# Power.net
KiCad netlist of a schematic drawn in Altium Designer
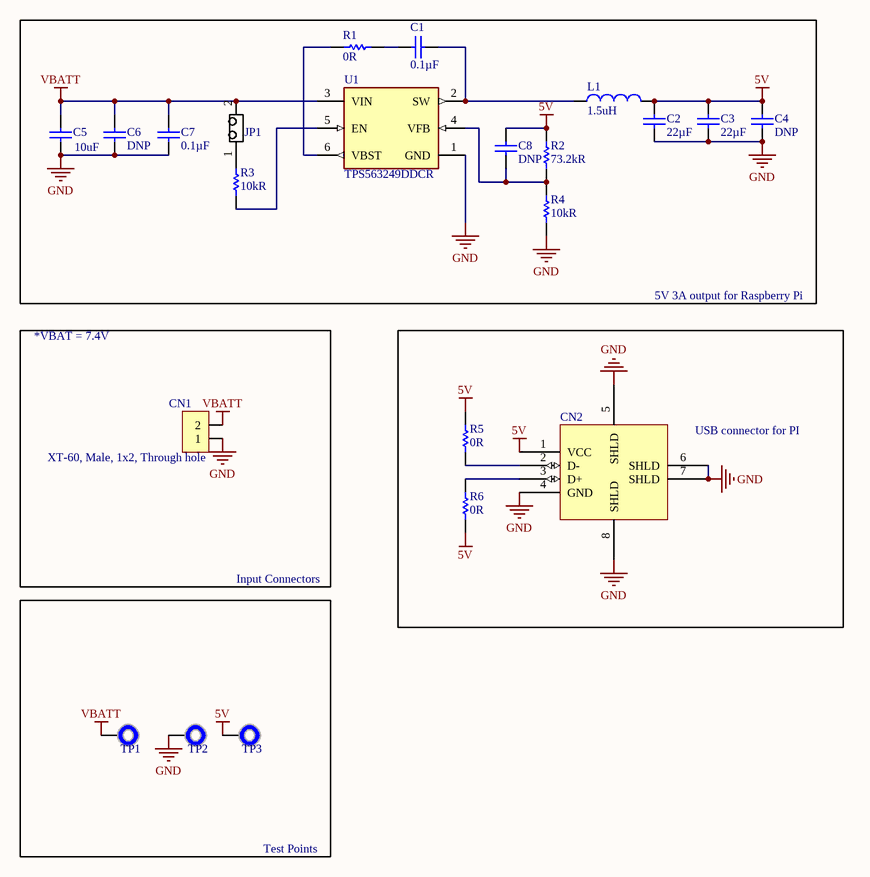
[diagram p0: Power.SchDoc]

(export (version "E")
  (design (tool "Eeschema 10.0.6"))
  (components
    (comp (ref "C1")
      (value "0.1uF, 50V, 10%, X7R, 0603")
      (footprint "CAPC1608N(0603\")")
      (description "0.1µF ±10% Ceramic Capacitor X7R 0603 (1608 Metric)")
      (fields (field (name "CAPACITANCE") "0.1µF") (field (name "CREATED BY") "Poorna Chander Kalidas"))
      (libsource (lib "") (part "Symbol_3"))
    )
    (comp (ref "C2")
      (value "22µF")
      (footprint "CAPC2012N(0805\")")
      (description "Capacitor, Ceramic, 35V, +/- 20%, 0805 SMD, X5R")
      (fields (field (name "Comment") "22uF 35V 0805 SMD, Ceramic") (field (name "PUBLISHER") "AUVic"))
      (libsource (lib "") (part "Symbol_2"))
    )
    (comp (ref "C3")
      (value "22µF")
      (footprint "CAPC2012N(0805\")")
      (description "Capacitor, Ceramic, 35V, +/- 20%, 0805 SMD, X5R")
      (fields (field (name "Comment") "22uF 35V 0805 SMD, Ceramic") (field (name "PUBLISHER") "AUVic"))
      (libsource (lib "") (part "Symbol_2"))
    )
    (comp (ref "C4")
      (value "DNP")
      (footprint "CAPC1608N(0603\")")
      (description "Placeholder 0603 SMT Footprint")
      (fields
        (field (name "Comment") "Placeholder_Capacitor_0603")
        (field (name "MADE BY") "Ashwin Sira")
        (field (name "PUBLISHER") "AUVic")
      )
      (libsource (lib "") (part "Symbol_1"))
    )
    (comp (ref "C5")
      (value "10uF, 25V, X5R, 0805")
      (footprint "CAPC2013X12N")
      (description "0805 10 uF 25 V ±10% Tolerance X5R SMT Multilayer Ceramic Capacitor")
      (fields (field (name "CAPACITANCE") "10uF") (field (name "TOLERANCE") "10%"))
      (libsource (lib "AUVIC") (part "CAP"))
    )
    (comp (ref "C6")
      (value "DNP")
      (footprint "CAPC3216N(1206\")")
      (description "Placeholder 1206 SMT Footprint")
      (fields
        (field (name "Comment") "Placeholder_Capacitor_1206")
        (field (name "MADE BY") "Ashwin Sira")
        (field (name "PUBLISHER") "AUVic")
      )
      (libsource (lib "") (part "Symbol_1"))
    )
    (comp (ref "C7")
      (value "0.1uF, 50V, 10%, X7R, 0603")
      (footprint "CAPC1608N(0603\")")
      (description "0.1µF ±10% Ceramic Capacitor X7R 0603 (1608 Metric)")
      (fields (field (name "CAPACITANCE") "0.1µF") (field (name "CREATED BY") "Poorna Chander Kalidas"))
      (libsource (lib "") (part "Symbol_3"))
    )
    (comp (ref "C8")
      (value "DNP")
      (footprint "CAPC1608N(0603\")")
      (description "Placeholder 0603 SMT Footprint")
      (fields
        (field (name "Comment") "Placeholder_Capacitor_0603")
        (field (name "MADE BY") "Ashwin Sira")
        (field (name "PUBLISHER") "AUVic")
      )
      (libsource (lib "") (part "Symbol_1"))
    )
    (comp (ref "CN1")
      (value "XT-60, Male, 1x2, Through hole")
      (footprint "XT-60 Male")
      (fields (field (name "PUBLISHER") "Andy Bates"))
      (libsource (lib "") (part "Symbol_4"))
    )
    (comp (ref "CN2")
      (value "USB - Type A Female")
      (footprint "USB - Type A Female-Footprint-1")
      (description "USB - Type A Female USB 2.0 THT")
      (fields (field (name "LCSC PART #") "C168725") (field (name "CREATED BY") "Miguel Manguerra"))
      (libsource (lib "AUVIC") (part "USB - Type A Female"))
    )
    (comp (ref "JP1")
      (value "1x2 Male Header")
      (footprint "2X1 Males Header")
      (fields (field (name "MADE BY") "Andy Bates"))
      (libsource (lib "AUVIC") (part "1x2 Male Header"))
    )
    (comp (ref "L1")
      (value "DFE252012P-1R5M=P2")
      (footprint "INDC2520X12N")
      (description "Ind Metal Alloy Shielded 1.5uH 20% 1MHz Powdered Iron 2.6A 1008 T/R")
      (fields (field (name "INDUCTANCE") "1.5uH") (field (name "TOLERANCE") "20%"))
      (libsource (lib "") (part "Symbol_5"))
    )
    (comp (ref "R1")
      (value "0R")
      (footprint "RESC1608N(0603\")")
      (description "0R, 1%, 1/10W, 0603 SMD")
      (fields (field (name "MADE BY") "Ashwin Sira"))
      (libsource (lib "AUVIC") (part "Symbol"))
    )
    (comp (ref "R2")
      (value "ERJ-3EKF7322V")
      (footprint "RESC1608X55X30LL15T15")
      (description "Res Thick Film 0603 73.2K Ohm 1% 0.1W(1/10W) ±100ppm/C Pad SMD Automotive T/R")
      (fields (field (name "TOLERANCE") "1%") (field (name "RESISTANCE") "73.2kR"))
      (libsource (lib "AUVIC") (part "RES"))
    )
    (comp (ref "R3")
      (value "RC0603FR-0710KL")
      (footprint "RESC1608X55X25ML10T15")
      (description "Res General Purpose Thick Film 0603 10K Ohm 1% 1/10W ±100ppm/°C Molded SMD Paper T/R")
      (fields (field (name "RESISTANCE") "10kR") (field (name "TOLERANCE") "1%"))
      (libsource (lib "AUVIC") (part "RES-2"))
    )
    (comp (ref "R4")
      (value "RC0603FR-0710KL")
      (footprint "RESC1608X55X25ML10T15")
      (description "Res General Purpose Thick Film 0603 10K Ohm 1% 1/10W ±100ppm/°C Molded SMD Paper T/R")
      (fields (field (name "RESISTANCE") "10kR") (field (name "TOLERANCE") "1%"))
      (libsource (lib "AUVIC") (part "RES-2"))
    )
    (comp (ref "R5")
      (value "0R")
      (footprint "RESC1608N(0603\")")
      (description "0R, 1%, 1/10W, 0603 SMD")
      (fields (field (name "MADE BY") "Ashwin Sira"))
      (libsource (lib "AUVIC") (part "Symbol"))
    )
    (comp (ref "R6")
      (value "0R")
      (footprint "RESC1608N(0603\")")
      (description "0R, 1%, 1/10W, 0603 SMD")
      (fields (field (name "MADE BY") "Ashwin Sira"))
      (libsource (lib "AUVIC") (part "Symbol"))
    )
    (comp (ref "TP1")
      (value "Plated Hole, 1mm")
      (footprint "PLATED_HOLE_1mm")
      (fields
        (field (name "CREATED BY") "Ashwin Sira")
        (field (name "SOURCE") "AUVic_Integrated_Library_Virtual_Components.SchLib")
        (field (name "PUBLISHER") "AUVic")
      )
      (libsource (lib "AUVIC") (part "Plated Hole, 1mm"))
    )
    (comp (ref "TP2")
      (value "Plated Hole, 1mm")
      (footprint "PLATED_HOLE_1mm")
      (fields
        (field (name "CREATED BY") "Ashwin Sira")
        (field (name "SOURCE") "AUVic_Integrated_Library_Virtual_Components.SchLib")
        (field (name "PUBLISHER") "AUVic")
      )
      (libsource (lib "AUVIC") (part "Plated Hole, 1mm"))
    )
    (comp (ref "TP3")
      (value "Plated Hole, 1mm")
      (footprint "PLATED_HOLE_1mm")
      (fields
        (field (name "CREATED BY") "Ashwin Sira")
        (field (name "SOURCE") "AUVic_Integrated_Library_Virtual_Components.SchLib")
        (field (name "PUBLISHER") "AUVic")
      )
      (libsource (lib "AUVIC") (part "Plated Hole, 1mm"))
    )
    (comp (ref "U1")
      (value "TPS563249DDCR")
      (footprint "FP-DDC0005A-IPC_B")
      (description "17-V, 3-A, constant 1.4-MHz synchronous step-down voltage regulator 6-SOT-23-THIN -40 to 125")
      (libsource (lib "AUVIC") (part "2eeca152cdac1d6057925bf7033f176"))
    )
  )
  (nets
    (net (code "1") (name "5V") (class "Default")
      (node (ref "C2") (pin "2") (pinfunction "Cathode_2") (pintype "passive"))
      (node (ref "C3") (pin "2") (pinfunction "Cathode_2") (pintype "passive"))
      (node (ref "C4") (pin "2") (pinfunction "Cathode_2") (pintype "passive"))
      (node (ref "C8") (pin "1") (pinfunction "Anode_1") (pintype "passive"))
      (node (ref "CN2") (pin "1") (pinfunction "VCC_1") (pintype "power_in"))
      (node (ref "L1") (pin "2") (pinfunction "2_2") (pintype "passive"))
      (node (ref "R2") (pin "2") (pinfunction "2_2") (pintype "passive"))
      (node (ref "R5") (pin "1") (pinfunction "1_1") (pintype "passive"))
      (node (ref "R6") (pin "2") (pinfunction "2_2") (pintype "passive"))
      (node (ref "TP3") (pin "1") (pinfunction "1_1") (pintype "passive"))
    )
    (net (code "2") (name "GND") (class "Default")
      (node (ref "C2") (pin "1") (pinfunction "Anode_1") (pintype "passive"))
      (node (ref "C3") (pin "1") (pinfunction "Anode_1") (pintype "passive"))
      (node (ref "C4") (pin "1") (pinfunction "Anode_1") (pintype "passive"))
      (node (ref "C5") (pin "2") (pinfunction "2_2") (pintype "passive"))
      (node (ref "C6") (pin "1") (pinfunction "Anode_1") (pintype "passive"))
      (node (ref "C7") (pin "1") (pinfunction "Anode_1") (pintype "passive"))
      (node (ref "CN1") (pin "1") (pinfunction "1_1") (pintype "passive"))
      (node (ref "CN2") (pin "4") (pinfunction "GND_4") (pintype "power_in"))
      (node (ref "CN2") (pin "5") (pinfunction "SHLD_5") (pintype "passive"))
      (node (ref "CN2") (pin "6") (pinfunction "SHLD_6") (pintype "passive"))
      (node (ref "CN2") (pin "7") (pinfunction "SHLD_7") (pintype "passive"))
      (node (ref "CN2") (pin "8") (pinfunction "SHLD_8") (pintype "passive"))
      (node (ref "R4") (pin "1") (pinfunction "1_1") (pintype "passive"))
      (node (ref "TP2") (pin "1") (pinfunction "1_1") (pintype "passive"))
      (node (ref "U1") (pin "1") (pinfunction "GND_1") (pintype "power_in"))
    )
    (net (code "3") (name "Net-(C1-Anode)") (class "Default")
      (node (ref "C1") (pin "1") (pinfunction "Anode_1") (pintype "passive"))
      (node (ref "L1") (pin "1") (pinfunction "1_1") (pintype "passive"))
      (node (ref "U1") (pin "2") (pinfunction "SW_2") (pintype "output"))
    )
    (net (code "4") (name "Net-(C1-Cathode)") (class "Default")
      (node (ref "C1") (pin "2") (pinfunction "Cathode_2") (pintype "passive"))
      (node (ref "R1") (pin "2") (pinfunction "2_2") (pintype "passive"))
    )
    (net (code "5") (name "Net-(C8-Cathode)") (class "Default")
      (node (ref "C8") (pin "2") (pinfunction "Cathode_2") (pintype "passive"))
      (node (ref "R2") (pin "1") (pinfunction "1_1") (pintype "passive"))
      (node (ref "R4") (pin "2") (pinfunction "2_2") (pintype "passive"))
      (node (ref "U1") (pin "4") (pinfunction "VFB_4") (pintype "input"))
    )
    (net (code "6") (name "Net-(CN2-D+)") (class "Default")
      (node (ref "CN2") (pin "3") (pinfunction "D+_3") (pintype "bidirectional"))
      (node (ref "R6") (pin "1") (pinfunction "1_1") (pintype "passive"))
    )
    (net (code "7") (name "Net-(CN2-D-)") (class "Default")
      (node (ref "CN2") (pin "2") (pinfunction "D-_2") (pintype "bidirectional"))
      (node (ref "R5") (pin "2") (pinfunction "2_2") (pintype "passive"))
    )
    (net (code "8") (name "Net-(JP1-Pad1)") (class "Default")
      (node (ref "JP1") (pin "1") (pinfunction "1_1") (pintype "passive"))
      (node (ref "R3") (pin "2") (pinfunction "2_2") (pintype "passive"))
    )
    (net (code "9") (name "Net-(U1-EN)") (class "Default")
      (node (ref "R3") (pin "1") (pinfunction "1_1") (pintype "passive"))
      (node (ref "U1") (pin "5") (pinfunction "EN_5") (pintype "input"))
    )
    (net (code "10") (name "Net-(U1-VBST)") (class "Default")
      (node (ref "R1") (pin "1") (pinfunction "1_1") (pintype "passive"))
      (node (ref "U1") (pin "6") (pinfunction "VBST_6") (pintype "output"))
    )
    (net (code "11") (name "VBATT") (class "Default")
      (node (ref "C5") (pin "1") (pinfunction "1_1") (pintype "passive"))
      (node (ref "C6") (pin "2") (pinfunction "Cathode_2") (pintype "passive"))
      (node (ref "C7") (pin "2") (pinfunction "Cathode_2") (pintype "passive"))
      (node (ref "CN1") (pin "2") (pinfunction "2_2") (pintype "passive"))
      (node (ref "JP1") (pin "2") (pinfunction "2_2") (pintype "passive"))
      (node (ref "TP1") (pin "1") (pinfunction "1_1") (pintype "passive"))
      (node (ref "U1") (pin "3") (pinfunction "VIN_3") (pintype "power_in"))
    )
  )
)
